# tamrin1Nima.net
KiCad netlist of a schematic drawn in Altium Designer
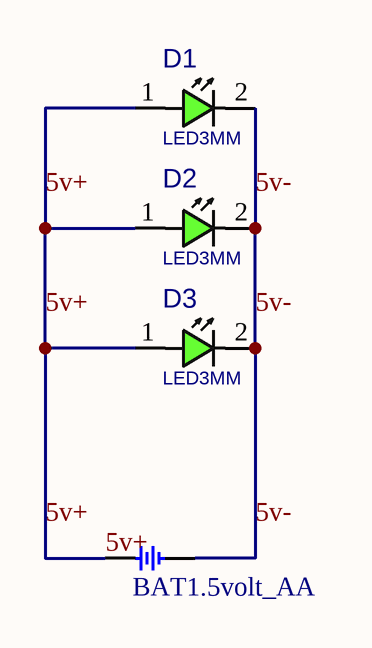
[diagram p0: tamrin1Nima.SchDoc]

(export (version "E")
  (design (tool "Eeschema 10.0.6"))
  (components
    (comp (ref "BT1")
      (value "BAT1.5volt_AA")
      (footprint "BTH_AA")
      (description "BATTERY HOLDER, AA")
      (fields (field (name "MANF_P#") "Keystone 82"))
      (libsource (lib "battery") (part "BATH_AA"))
    )
    (comp (ref "D1")
      (value "LED3MM")
      (footprint "LED3MM")
      (description "LED, THD, 3MM, GREEN")
      (fields (field (name "MANF") "MANF") (field (name "MANF_P#") "MANF_PART#"))
      (libsource (lib "led(diode)") (part "LED_THD_3MM"))
    )
    (comp (ref "D2")
      (value "LED3MM")
      (footprint "LED3MM")
      (description "LED, THD, 3MM, GREEN")
      (fields (field (name "MANF") "MANF") (field (name "MANF_P#") "MANF_PART#"))
      (libsource (lib "led(diode)") (part "LED_THD_3MM"))
    )
    (comp (ref "D3")
      (value "LED3MM")
      (footprint "LED3MM")
      (description "LED, THD, 3MM, GREEN")
      (fields (field (name "MANF") "MANF") (field (name "MANF_P#") "MANF_PART#"))
      (libsource (lib "led(diode)") (part "LED_THD_3MM"))
    )
  )
  (nets
    (net (code "1") (name "/5v+") (class "Default")
      (node (ref "BT1") (pin "1") (pinfunction "1_1") (pintype "passive"))
      (node (ref "D1") (pin "1") (pinfunction "ANODE_1") (pintype "passive"))
      (node (ref "D2") (pin "1") (pinfunction "ANODE_1") (pintype "passive"))
      (node (ref "D3") (pin "1") (pinfunction "ANODE_1") (pintype "passive"))
    )
    (net (code "2") (name "/5v-") (class "Default")
      (node (ref "BT1") (pin "2") (pinfunction "2_2") (pintype "passive"))
      (node (ref "D1") (pin "2") (pinfunction "CATHODE_2") (pintype "passive"))
      (node (ref "D2") (pin "2") (pinfunction "CATHODE_2") (pintype "passive"))
      (node (ref "D3") (pin "2") (pinfunction "CATHODE_2") (pintype "passive"))
    )
  )
)
